# 14-DPLL_1.net
KiCad netlist of a schematic drawn in Altium Designer
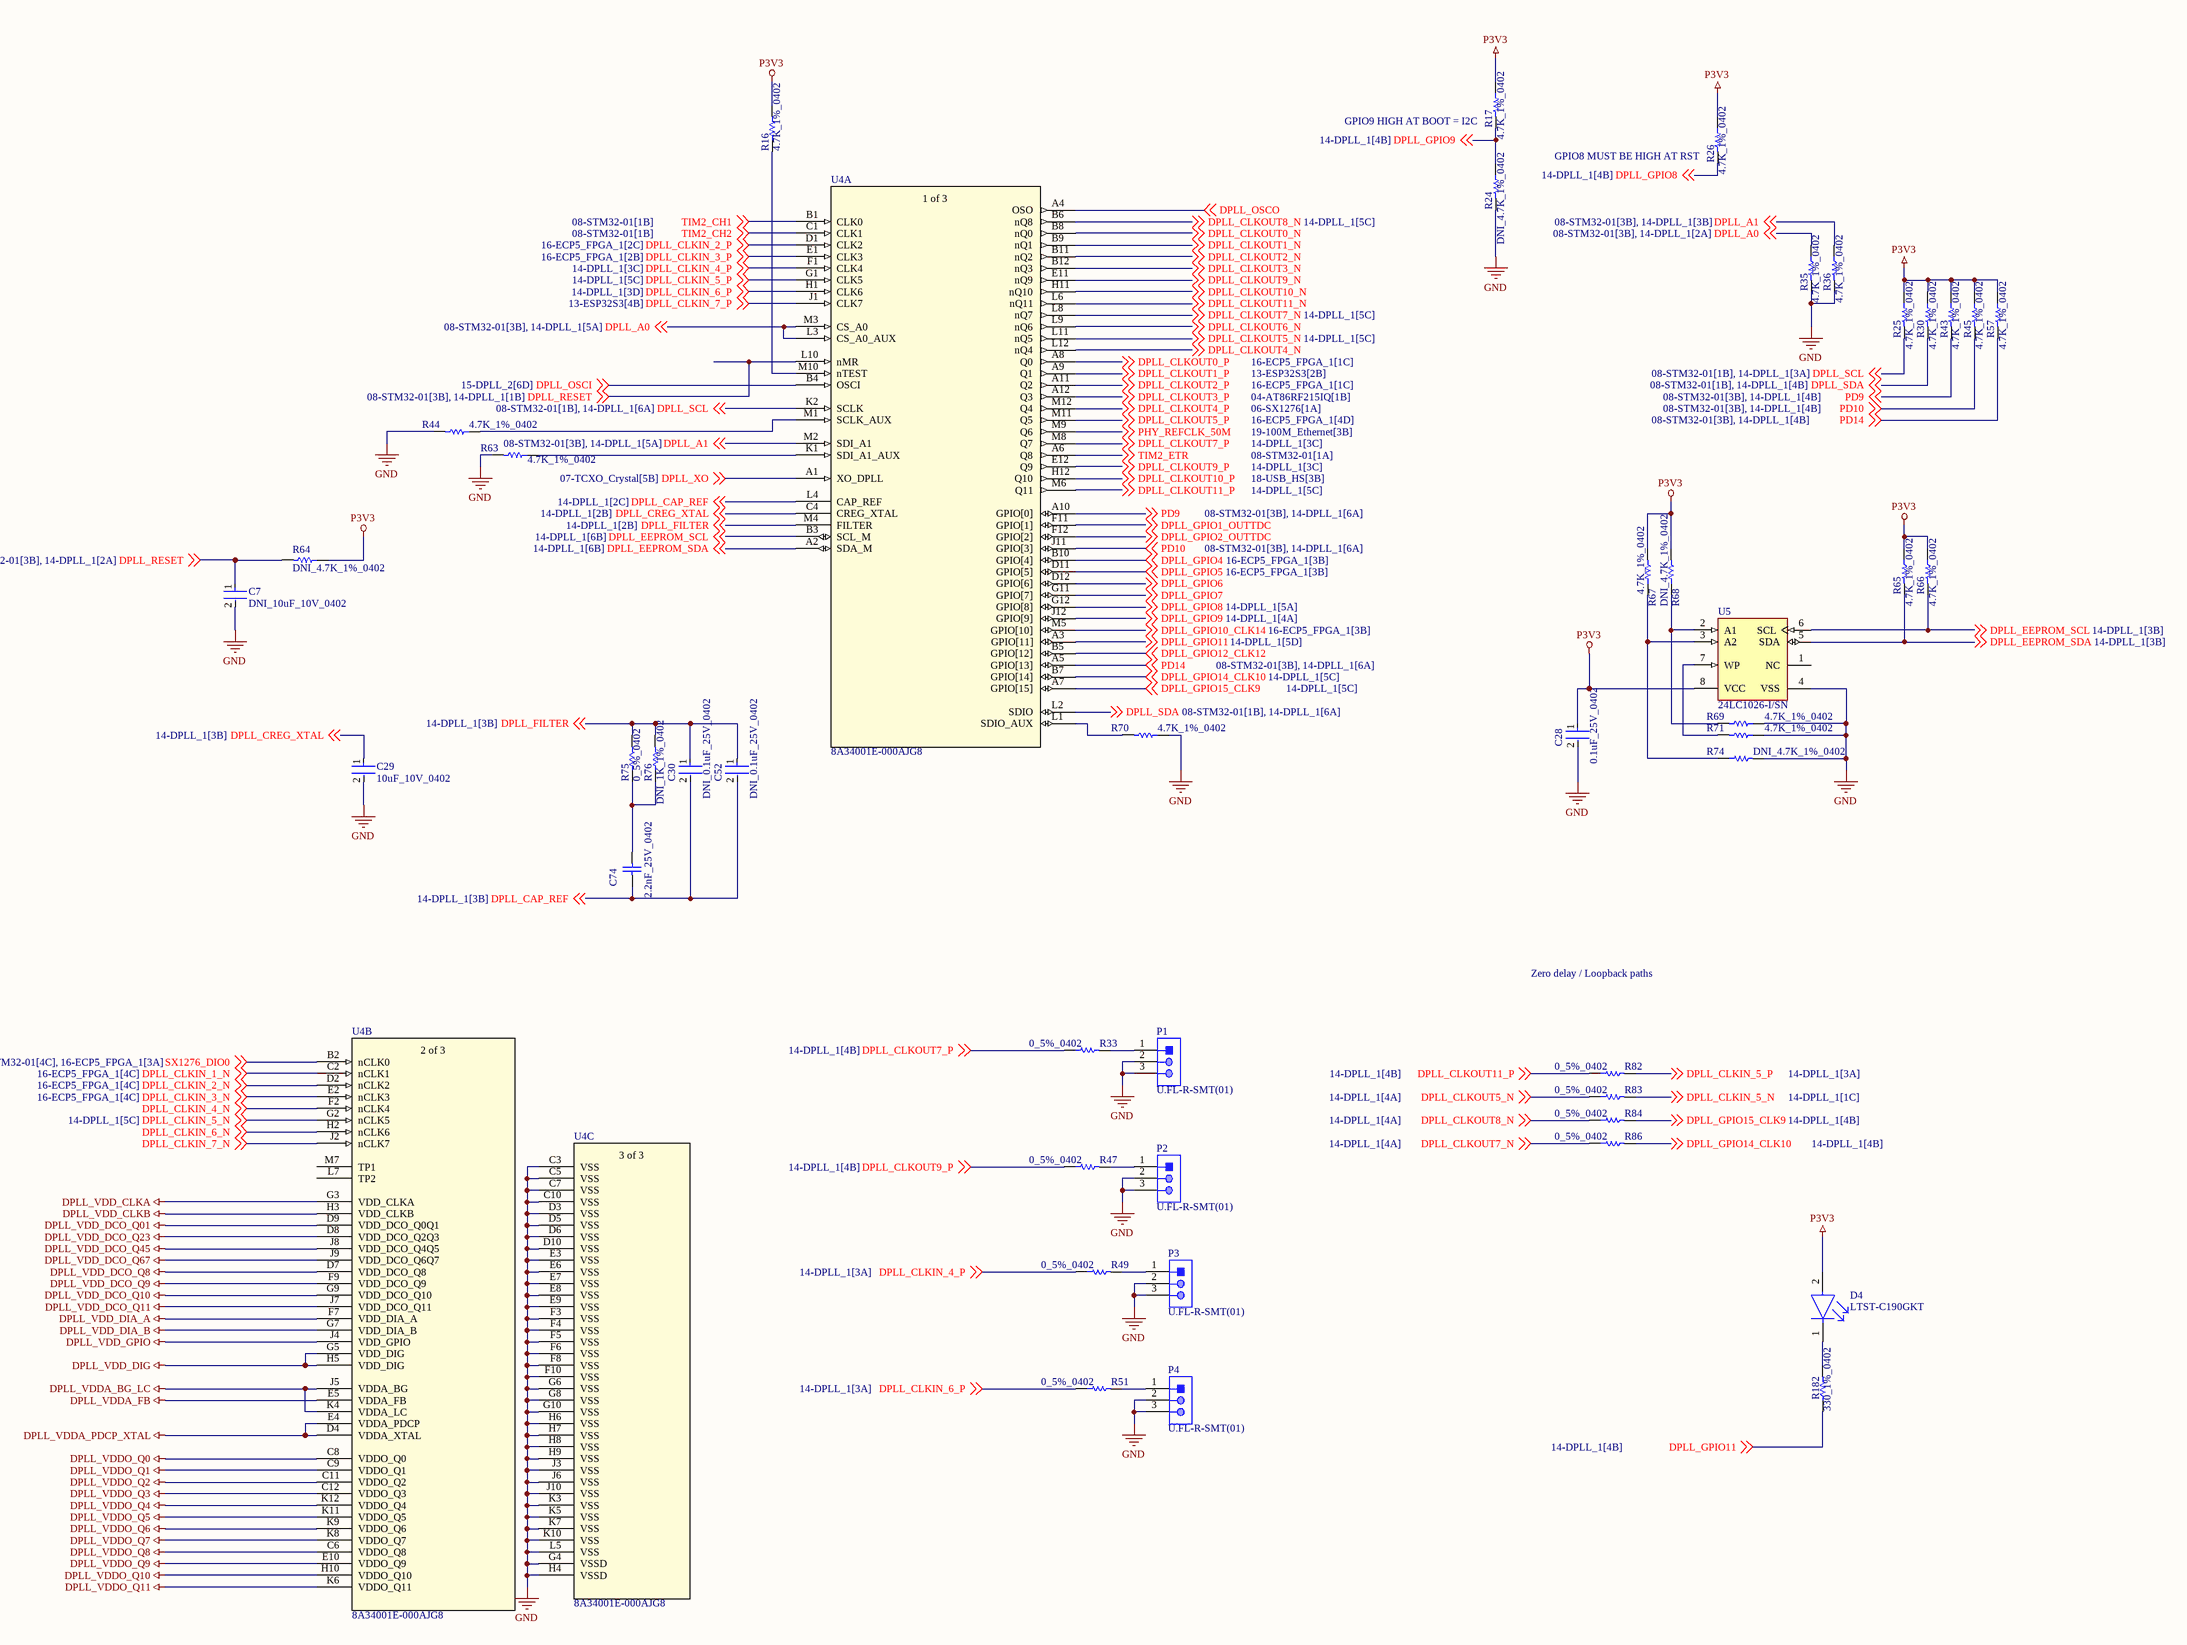
[diagram p0: 14-DPLL_1.SchDoc]

(export (version "E")
  (design (tool "Eeschema 10.0.6"))
  (components
    (comp (ref "C7")
      (value "DNI_10uF_10V_0402")
      (footprint "FP-CL05A106MP5NUNC-MFG")
      (description "CAP CER 10UF 10V X5R 0402")
      (fields
        (field (name "OCTOPART") "https://octopart.com/cl05a106mp5nunc-samsung-22457395")
        (field (name "TOLERANCE") "20%")
      )
      (libsource (lib "Altium Content Vault") (part "b4654b650e69147ec39a6b967a45e02"))
    )
    (comp (ref "C28")
      (value "0.1uF_25V_0402")
      (footprint "FP-0402-L_1_0_1-W_0_5_0_1-IPC_C")
      (description "General Purpose Ceramic Capacitor, 0402, 100nF, 10%, X7R, 15%, 25V")
      (fields (field (name "VOLTAGE") "25V") (field (name "TOLERANCE") "10%"))
      (libsource (lib "Altium Content Vault") (part "b4654b650e69147ec39a6b967a45e02"))
    )
    (comp (ref "C29")
      (value "10uF_10V_0402")
      (footprint "FP-CL05A106MP5NUNC-MFG")
      (description "CAP CER 10UF 10V X5R 0402")
      (fields
        (field (name "OCTOPART") "https://octopart.com/cl05a106mp5nunc-samsung-22457395")
        (field (name "TOLERANCE") "20%")
      )
      (libsource (lib "Altium Content Vault") (part "b4654b650e69147ec39a6b967a45e02"))
    )
    (comp (ref "C30")
      (value "DNI_0.1uF_25V_0402")
      (footprint "FP-0402-L_1_0_1-W_0_5_0_1-IPC_C")
      (description "General Purpose Ceramic Capacitor, 0402, 100nF, 10%, X7R, 15%, 25V")
      (fields (field (name "VOLTAGE") "25V") (field (name "TOLERANCE") "10%"))
      (libsource (lib "Altium Content Vault") (part "b4654b650e69147ec39a6b967a45e02"))
    )
    (comp (ref "C52")
      (value "DNI_0.1uF_25V_0402")
      (footprint "FP-0402-L_1_0_1-W_0_5_0_1-IPC_C")
      (description "General Purpose Ceramic Capacitor, 0402, 100nF, 10%, X7R, 15%, 25V")
      (fields (field (name "VOLTAGE") "25V") (field (name "TOLERANCE") "10%"))
      (libsource (lib "Altium Content Vault") (part "b4654b650e69147ec39a6b967a45e02"))
    )
    (comp (ref "C74")
      (value "2.2nF_25V_0402")
      (footprint "CAPC1005X56X25LL10T15")
      (fields
        (field (name "MANUFACTURER") "AVX Interconnect / Elco")
        (field (name "PART NUMBER") "04025C222JAT2A")
      )
      (libsource (lib "Altium Content Vault") (part "CAP"))
    )
    (comp (ref "D4")
      (value "LTST-C190GKT")
      (footprint "FP-LTST-C190GKT-MFG")
      (description "LED GREEN CLEAR CHIP SMD")
      (fields (field (name "VOLTAGE") "2V"))
      (libsource (lib "Altium Content Vault") (part "8706943c75ba83719d021d2fdc84c58"))
    )
    (comp (ref "P1")
      (value "U.FL-R-SMT(01)")
      (footprint "HRS-U.FL-R-SMT(10)_V")
      (description "CONN RECPT ULTRA-MINI COAX SMD")
      (fields (field (name "MANUFACTURER") "Hirose Electric") (field (name "APPROVAL CATEGORY") "UL94V-0"))
      (libsource (lib "Altium Content Vault") (part "CN-1P-M-R3"))
    )
    (comp (ref "P2")
      (value "U.FL-R-SMT(01)")
      (footprint "HRS-U.FL-R-SMT(10)_V")
      (description "CONN RECPT ULTRA-MINI COAX SMD")
      (fields (field (name "MANUFACTURER") "Hirose Electric") (field (name "APPROVAL CATEGORY") "UL94V-0"))
      (libsource (lib "Altium Content Vault") (part "CN-1P-M-R3"))
    )
    (comp (ref "P3")
      (value "U.FL-R-SMT(01)")
      (footprint "HRS-U.FL-R-SMT(10)_V")
      (description "CONN RECPT ULTRA-MINI COAX SMD")
      (fields (field (name "MANUFACTURER") "Hirose Electric") (field (name "APPROVAL CATEGORY") "UL94V-0"))
      (libsource (lib "Altium Content Vault") (part "CN-1P-M-R3"))
    )
    (comp (ref "P4")
      (value "U.FL-R-SMT(01)")
      (footprint "HRS-U.FL-R-SMT(10)_V")
      (description "CONN RECPT ULTRA-MINI COAX SMD")
      (fields (field (name "MANUFACTURER") "Hirose Electric") (field (name "APPROVAL CATEGORY") "UL94V-0"))
      (libsource (lib "Altium Content Vault") (part "CN-1P-M-R3"))
    )
    (comp (ref "R16")
      (value "4.7K_1%_0402")
      (footprint "RESC1005X40X25NL10T10")
      (fields (field (name "MANUFACTURER") "Bourns") (field (name "PART NUMBER") "CR0402-FX-4701GLF"))
      (libsource (lib "Altium Content Vault") (part "RES"))
    )
    (comp (ref "R17")
      (value "4.7K_1%_0402")
      (footprint "RESC1005X40X25NL10T10")
      (fields (field (name "MANUFACTURER") "Bourns") (field (name "PART NUMBER") "CR0402-FX-4701GLF"))
      (libsource (lib "Altium Content Vault") (part "RES"))
    )
    (comp (ref "R24")
      (value "DNI_4.7K_1%_0402")
      (footprint "RESC1005X40X25NL10T10")
      (fields (field (name "MANUFACTURER") "Bourns") (field (name "PART NUMBER") "CR0402-FX-4701GLF"))
      (libsource (lib "Altium Content Vault") (part "RES"))
    )
    (comp (ref "R25")
      (value "4.7K_1%_0402")
      (footprint "RESC1005X40X25NL10T10")
      (fields (field (name "MANUFACTURER") "Bourns") (field (name "PART NUMBER") "CR0402-FX-4701GLF"))
      (libsource (lib "Altium Content Vault") (part "RES"))
    )
    (comp (ref "R26")
      (value "4.7K_1%_0402")
      (footprint "RESC1005X40X25NL10T10")
      (fields (field (name "MANUFACTURER") "Bourns") (field (name "PART NUMBER") "CR0402-FX-4701GLF"))
      (libsource (lib "Altium Content Vault") (part "RES"))
    )
    (comp (ref "R30")
      (value "4.7K_1%_0402")
      (footprint "RESC1005X40X25NL10T10")
      (fields (field (name "MANUFACTURER") "Bourns") (field (name "PART NUMBER") "CR0402-FX-4701GLF"))
      (libsource (lib "Altium Content Vault") (part "RES"))
    )
    (comp (ref "R33")
      (value "0_5%_0402")
      (footprint "RESC1005X40X25LL10T10")
      (fields (field (name "MANUFACTURER") "KOA Speer") (field (name "PART NUMBER") "RK73Z1ETTP"))
      (libsource (lib "Altium Content Vault") (part "RES"))
    )
    (comp (ref "R35")
      (value "4.7K_1%_0402")
      (footprint "RESC1005X40X25NL10T10")
      (fields (field (name "MANUFACTURER") "Bourns") (field (name "PART NUMBER") "CR0402-FX-4701GLF"))
      (libsource (lib "Altium Content Vault") (part "RES"))
    )
    (comp (ref "R36")
      (value "4.7K_1%_0402")
      (footprint "RESC1005X40X25NL10T10")
      (fields (field (name "MANUFACTURER") "Bourns") (field (name "PART NUMBER") "CR0402-FX-4701GLF"))
      (libsource (lib "Altium Content Vault") (part "RES"))
    )
    (comp (ref "R43")
      (value "4.7K_1%_0402")
      (footprint "RESC1005X40X25NL10T10")
      (fields (field (name "MANUFACTURER") "Bourns") (field (name "PART NUMBER") "CR0402-FX-4701GLF"))
      (libsource (lib "Altium Content Vault") (part "RES"))
    )
    (comp (ref "R44")
      (value "4.7K_1%_0402")
      (footprint "RESC1005X40X25NL10T10")
      (fields (field (name "MANUFACTURER") "Bourns") (field (name "PART NUMBER") "CR0402-FX-4701GLF"))
      (libsource (lib "Altium Content Vault") (part "RES"))
    )
    (comp (ref "R45")
      (value "4.7K_1%_0402")
      (footprint "RESC1005X40X25NL10T10")
      (fields (field (name "MANUFACTURER") "Bourns") (field (name "PART NUMBER") "CR0402-FX-4701GLF"))
      (libsource (lib "Altium Content Vault") (part "RES"))
    )
    (comp (ref "R47")
      (value "0_5%_0402")
      (footprint "RESC1005X40X25LL10T10")
      (fields (field (name "MANUFACTURER") "KOA Speer") (field (name "PART NUMBER") "RK73Z1ETTP"))
      (libsource (lib "Altium Content Vault") (part "RES"))
    )
    (comp (ref "R49")
      (value "0_5%_0402")
      (footprint "RESC1005X40X25LL10T10")
      (fields (field (name "MANUFACTURER") "KOA Speer") (field (name "PART NUMBER") "RK73Z1ETTP"))
      (libsource (lib "Altium Content Vault") (part "RES"))
    )
    (comp (ref "R51")
      (value "0_5%_0402")
      (footprint "RESC1005X40X25LL10T10")
      (fields (field (name "MANUFACTURER") "KOA Speer") (field (name "PART NUMBER") "RK73Z1ETTP"))
      (libsource (lib "Altium Content Vault") (part "RES"))
    )
    (comp (ref "R57")
      (value "4.7K_1%_0402")
      (footprint "RESC1005X40X25NL10T10")
      (fields (field (name "MANUFACTURER") "Bourns") (field (name "PART NUMBER") "CR0402-FX-4701GLF"))
      (libsource (lib "Altium Content Vault") (part "RES"))
    )
    (comp (ref "R63")
      (value "4.7K_1%_0402")
      (footprint "RESC1005X40X25NL10T10")
      (fields (field (name "MANUFACTURER") "Bourns") (field (name "PART NUMBER") "CR0402-FX-4701GLF"))
      (libsource (lib "Altium Content Vault") (part "RES"))
    )
    (comp (ref "R64")
      (value "DNI_4.7K_1%_0402")
      (footprint "RESC1005X40X25NL10T10")
      (fields (field (name "MANUFACTURER") "Bourns") (field (name "PART NUMBER") "CR0402-FX-4701GLF"))
      (libsource (lib "Altium Content Vault") (part "RES"))
    )
    (comp (ref "R65")
      (value "4.7K_1%_0402")
      (footprint "RESC1005X40X25NL10T10")
      (fields (field (name "MANUFACTURER") "Bourns") (field (name "PART NUMBER") "CR0402-FX-4701GLF"))
      (libsource (lib "Altium Content Vault") (part "RES"))
    )
    (comp (ref "R66")
      (value "4.7K_1%_0402")
      (footprint "RESC1005X40X25NL10T10")
      (fields (field (name "MANUFACTURER") "Bourns") (field (name "PART NUMBER") "CR0402-FX-4701GLF"))
      (libsource (lib "Altium Content Vault") (part "RES"))
    )
    (comp (ref "R67")
      (value "4.7K_1%_0402")
      (footprint "RESC1005X40X25NL10T10")
      (fields (field (name "MANUFACTURER") "Bourns") (field (name "PART NUMBER") "CR0402-FX-4701GLF"))
      (libsource (lib "Altium Content Vault") (part "RES"))
    )
    (comp (ref "R68")
      (value "DNI_4.7K_1%_0402")
      (footprint "RESC1005X40X25NL10T10")
      (fields (field (name "MANUFACTURER") "Bourns") (field (name "PART NUMBER") "CR0402-FX-4701GLF"))
      (libsource (lib "Altium Content Vault") (part "RES"))
    )
    (comp (ref "R69")
      (value "4.7K_1%_0402")
      (footprint "RESC1005X40X25NL10T10")
      (fields (field (name "MANUFACTURER") "Bourns") (field (name "PART NUMBER") "CR0402-FX-4701GLF"))
      (libsource (lib "Altium Content Vault") (part "RES"))
    )
    (comp (ref "R70")
      (value "4.7K_1%_0402")
      (footprint "RESC1005X40X25NL10T10")
      (fields (field (name "MANUFACTURER") "Bourns") (field (name "PART NUMBER") "CR0402-FX-4701GLF"))
      (libsource (lib "Altium Content Vault") (part "RES"))
    )
    (comp (ref "R71")
      (value "4.7K_1%_0402")
      (footprint "RESC1005X40X25NL10T10")
      (fields (field (name "MANUFACTURER") "Bourns") (field (name "PART NUMBER") "CR0402-FX-4701GLF"))
      (libsource (lib "Altium Content Vault") (part "RES"))
    )
    (comp (ref "R74")
      (value "DNI_4.7K_1%_0402")
      (footprint "RESC1005X40X25NL10T10")
      (fields (field (name "MANUFACTURER") "Bourns") (field (name "PART NUMBER") "CR0402-FX-4701GLF"))
      (libsource (lib "Altium Content Vault") (part "RES"))
    )
    (comp (ref "R75")
      (value "0_5%_0402")
      (footprint "RESC1005X40X25LL10T10")
      (fields (field (name "MANUFACTURER") "KOA Speer") (field (name "PART NUMBER") "RK73Z1ETTP"))
      (libsource (lib "Altium Content Vault") (part "RES"))
    )
    (comp (ref "R76")
      (value "DNI_1K_1%_0402")
      (footprint "RESC1005X40X25NL05T05")
      (fields (field (name "MANUFACTURER") "Vishay Dale") (field (name "PART NUMBER") "CRCW04021K00FKTD"))
      (libsource (lib "Altium Content Vault") (part "RES"))
    )
    (comp (ref "R82")
      (value "0_5%_0402")
      (footprint "RESC1005X40X25LL10T10")
      (fields (field (name "MANUFACTURER") "KOA Speer") (field (name "PART NUMBER") "RK73Z1ETTP"))
      (libsource (lib "Altium Content Vault") (part "RES"))
    )
    (comp (ref "R83")
      (value "0_5%_0402")
      (footprint "RESC1005X40X25LL10T10")
      (fields (field (name "MANUFACTURER") "KOA Speer") (field (name "PART NUMBER") "RK73Z1ETTP"))
      (libsource (lib "Altium Content Vault") (part "RES"))
    )
    (comp (ref "R84")
      (value "0_5%_0402")
      (footprint "RESC1005X40X25LL10T10")
      (fields (field (name "MANUFACTURER") "KOA Speer") (field (name "PART NUMBER") "RK73Z1ETTP"))
      (libsource (lib "Altium Content Vault") (part "RES"))
    )
    (comp (ref "R86")
      (value "0_5%_0402")
      (footprint "RESC1005X40X25LL10T10")
      (fields (field (name "MANUFACTURER") "KOA Speer") (field (name "PART NUMBER") "RK73Z1ETTP"))
      (libsource (lib "Altium Content Vault") (part "RES"))
    )
    (comp (ref "R182")
      (value "330_1%_0402")
      (footprint "RESC1005X40X25NL10T10")
      (fields (field (name "MANUFACTURER") "Panasonic") (field (name "PART NUMBER") "ERA-2AED331X"))
      (libsource (lib "Altium Content Vault") (part "RES"))
    )
    (comp (ref "U4")
      (value "8A34001E-000AJG8")
      (footprint "144-CABGA_REN")
      (description "No Description Available")
      (fields (field (name "COPYRIGHT") "Copyright (C) 2024 Ultra Librarian. All rights reserved."))
      (libsource (lib "8A34001E-000AJG8") (part "8A34001E-000AJG8"))
    )
    (comp (ref "U5")
      (value "24LC1026-I/SN")
      (footprint "MCHP-SOIC-SN8_N")
      (description "1024K bits I2C™ Serial EEPROM, 2.5 to 5.5 V, 400 kHz, -40 to 85 degC, 8-pin SOIC (SN8), Tube")
      (fields (field (name "MANUFACTURER") "Microchip"))
      (libsource (lib "Altium Content Vault") (part "MCHP-24LC1026-SOIC-8"))
    )
  )
  (nets
    (net (code "1") (name "DPLL_A0") (class "Default")
      (node (ref "R35") (pin "1") (pinfunction "1_1") (pintype "passive"))
      (node (ref "U4") (pin "L3") (pinfunction "CS_A0_AUX_L3") (pintype "input"))
      (node (ref "U4") (pin "M3") (pinfunction "CS_A0_M3") (pintype "input"))
    )
    (net (code "2") (name "DPLL_A1") (class "Default")
      (node (ref "R36") (pin "1") (pinfunction "1_1") (pintype "passive"))
      (node (ref "U4") (pin "M2") (pinfunction "SDI_A1_M2") (pintype "input"))
    )
    (net (code "3") (name "DPLL_CAP_REF") (class "Default")
      (node (ref "C30") (pin "2") (pinfunction "2_2") (pintype "passive"))
      (node (ref "C52") (pin "2") (pinfunction "2_2") (pintype "passive"))
      (node (ref "C74") (pin "1") (pinfunction "1_1") (pintype "passive"))
      (node (ref "U4") (pin "L4") (pinfunction "CAP_REF_L4") (pintype "passive"))
    )
    (net (code "4") (name "DPLL_CLKIN_1_N") (class "Default")
      (node (ref "U4") (pin "C2") (pinfunction "nCLK1_C2") (pintype "input"))
    )
    (net (code "5") (name "DPLL_CLKIN_2_N") (class "Default")
      (node (ref "U4") (pin "D2") (pinfunction "nCLK2_D2") (pintype "input"))
    )
    (net (code "6") (name "DPLL_CLKIN_2_P") (class "Default")
      (node (ref "U4") (pin "D1") (pinfunction "CLK2_D1") (pintype "input"))
    )
    (net (code "7") (name "DPLL_CLKIN_3_N") (class "Default")
      (node (ref "U4") (pin "E2") (pinfunction "nCLK3_E2") (pintype "input"))
    )
    (net (code "8") (name "DPLL_CLKIN_3_P") (class "Default")
      (node (ref "U4") (pin "E1") (pinfunction "CLK3_E1") (pintype "input"))
    )
    (net (code "9") (name "DPLL_CLKIN_4_N") (class "Default")
      (node (ref "U4") (pin "F2") (pinfunction "nCLK4_F2") (pintype "input"))
    )
    (net (code "10") (name "DPLL_CLKIN_4_P") (class "Default")
      (node (ref "R49") (pin "1") (pinfunction "1_1") (pintype "passive"))
      (node (ref "U4") (pin "F1") (pinfunction "CLK4_F1") (pintype "input"))
    )
    (net (code "11") (name "DPLL_CLKIN_5_N") (class "Default")
      (node (ref "R83") (pin "2") (pinfunction "2_2") (pintype "passive"))
      (node (ref "U4") (pin "G2") (pinfunction "nCLK5_G2") (pintype "input"))
    )
    (net (code "12") (name "DPLL_CLKIN_5_P") (class "Default")
      (node (ref "R82") (pin "2") (pinfunction "2_2") (pintype "passive"))
      (node (ref "U4") (pin "G1") (pinfunction "CLK5_G1") (pintype "input"))
    )
    (net (code "13") (name "DPLL_CLKIN_6_N") (class "Default")
      (node (ref "U4") (pin "H2") (pinfunction "nCLK6_H2") (pintype "input"))
    )
    (net (code "14") (name "DPLL_CLKIN_6_P") (class "Default")
      (node (ref "R51") (pin "1") (pinfunction "1_1") (pintype "passive"))
      (node (ref "U4") (pin "H1") (pinfunction "CLK6_H1") (pintype "input"))
    )
    (net (code "15") (name "DPLL_CLKIN_7_N") (class "Default")
      (node (ref "U4") (pin "J2") (pinfunction "nCLK7_J2") (pintype "input"))
    )
    (net (code "16") (name "DPLL_CLKIN_7_P") (class "Default")
      (node (ref "U4") (pin "J1") (pinfunction "CLK7_J1") (pintype "input"))
    )
    (net (code "17") (name "DPLL_CLKOUT0_N") (class "Default")
      (node (ref "U4") (pin "B8") (pinfunction "nQ0_B8") (pintype "output"))
    )
    (net (code "18") (name "DPLL_CLKOUT0_P") (class "Default")
      (node (ref "U4") (pin "A8") (pinfunction "Q0_A8") (pintype "output"))
    )
    (net (code "19") (name "DPLL_CLKOUT1_N") (class "Default")
      (node (ref "U4") (pin "B9") (pinfunction "nQ1_B9") (pintype "output"))
    )
    (net (code "20") (name "DPLL_CLKOUT1_P") (class "Default")
      (node (ref "U4") (pin "A9") (pinfunction "Q1_A9") (pintype "output"))
    )
    (net (code "21") (name "DPLL_CLKOUT2_N") (class "Default")
      (node (ref "U4") (pin "B11") (pinfunction "nQ2_B11") (pintype "output"))
    )
    (net (code "22") (name "DPLL_CLKOUT2_P") (class "Default")
      (node (ref "U4") (pin "A11") (pinfunction "Q2_A11") (pintype "output"))
    )
    (net (code "23") (name "DPLL_CLKOUT3_N") (class "Default")
      (node (ref "U4") (pin "B12") (pinfunction "nQ3_B12") (pintype "output"))
    )
    (net (code "24") (name "DPLL_CLKOUT3_P") (class "Default")
      (node (ref "U4") (pin "A12") (pinfunction "Q3_A12") (pintype "output"))
    )
    (net (code "25") (name "DPLL_CLKOUT4_N") (class "Default")
      (node (ref "U4") (pin "L12") (pinfunction "nQ4_L12") (pintype "output"))
    )
    (net (code "26") (name "DPLL_CLKOUT4_P") (class "Default")
      (node (ref "U4") (pin "M12") (pinfunction "Q4_M12") (pintype "output"))
    )
    (net (code "27") (name "DPLL_CLKOUT5_N") (class "Default")
      (node (ref "R83") (pin "1") (pinfunction "1_1") (pintype "passive"))
      (node (ref "U4") (pin "L11") (pinfunction "nQ5_L11") (pintype "output"))
    )
    (net (code "28") (name "DPLL_CLKOUT5_P") (class "Default")
      (node (ref "U4") (pin "M11") (pinfunction "Q5_M11") (pintype "output"))
    )
    (net (code "29") (name "DPLL_CLKOUT6_N") (class "Default")
      (node (ref "U4") (pin "L9") (pinfunction "nQ6_L9") (pintype "output"))
    )
    (net (code "30") (name "DPLL_CLKOUT7_N") (class "Default")
      (node (ref "R86") (pin "1") (pinfunction "1_1") (pintype "passive"))
      (node (ref "U4") (pin "L8") (pinfunction "nQ7_L8") (pintype "output"))
    )
    (net (code "31") (name "DPLL_CLKOUT7_P") (class "Default")
      (node (ref "R33") (pin "1") (pinfunction "1_1") (pintype "passive"))
      (node (ref "U4") (pin "M8") (pinfunction "Q7_M8") (pintype "output"))
    )
    (net (code "32") (name "DPLL_CLKOUT8_N") (class "Default")
      (node (ref "R84") (pin "1") (pinfunction "1_1") (pintype "passive"))
      (node (ref "U4") (pin "B6") (pinfunction "nQ8_B6") (pintype "output"))
    )
    (net (code "33") (name "DPLL_CLKOUT9_N") (class "Default")
      (node (ref "U4") (pin "E11") (pinfunction "nQ9_E11") (pintype "output"))
    )
    (net (code "34") (name "DPLL_CLKOUT9_P") (class "Default")
      (node (ref "R47") (pin "1") (pinfunction "1_1") (pintype "passive"))
      (node (ref "U4") (pin "E12") (pinfunction "Q9_E12") (pintype "output"))
    )
    (net (code "35") (name "DPLL_CLKOUT10_N") (class "Default")
      (node (ref "U4") (pin "H11") (pinfunction "nQ10_H11") (pintype "output"))
    )
    (net (code "36") (name "DPLL_CLKOUT10_P") (class "Default")
      (node (ref "U4") (pin "H12") (pinfunction "Q10_H12") (pintype "output"))
    )
    (net (code "37") (name "DPLL_CLKOUT11_N") (class "Default")
      (node (ref "U4") (pin "L6") (pinfunction "nQ11_L6") (pintype "output"))
    )
    (net (code "38") (name "DPLL_CLKOUT11_P") (class "Default")
      (node (ref "R82") (pin "1") (pinfunction "1_1") (pintype "passive"))
      (node (ref "U4") (pin "M6") (pinfunction "Q11_M6") (pintype "output"))
    )
    (net (code "39") (name "DPLL_CREG_XTAL") (class "Default")
      (node (ref "C29") (pin "1") (pinfunction "1_1") (pintype "passive"))
      (node (ref "U4") (pin "C4") (pinfunction "CREG_XTAL_C4") (pintype "passive"))
    )
    (net (code "40") (name "DPLL_EEPROM_SCL") (class "Default")
      (node (ref "R66") (pin "2") (pinfunction "2_2") (pintype "passive"))
      (node (ref "U4") (pin "B3") (pinfunction "SCL_M_B3") (pintype "bidirectional"))
      (node (ref "U5") (pin "6") (pinfunction "SCL_6") (pintype "input"))
    )
    (net (code "41") (name "DPLL_EEPROM_SDA") (class "Default")
      (node (ref "R65") (pin "2") (pinfunction "2_2") (pintype "passive"))
      (node (ref "U4") (pin "A2") (pinfunction "SDA_M_A2") (pintype "bidirectional"))
      (node (ref "U5") (pin "5") (pinfunction "SDA_5") (pintype "bidirectional"))
    )
    (net (code "42") (name "DPLL_FILTER") (class "Default")
      (node (ref "C30") (pin "1") (pinfunction "1_1") (pintype "passive"))
      (node (ref "C52") (pin "1") (pinfunction "1_1") (pintype "passive"))
      (node (ref "R75") (pin "2") (pinfunction "2_2") (pintype "passive"))
      (node (ref "R76") (pin "2") (pinfunction "2_2") (pintype "passive"))
      (node (ref "U4") (pin "M4") (pinfunction "FILTER_M4") (pintype "passive"))
    )
    (net (code "43") (name "DPLL_GPIO1_OUTTDC") (class "Default")
      (node (ref "U4") (pin "F11") (pinfunction "GPIO[1]_F11") (pintype "bidirectional"))
    )
    (net (code "44") (name "DPLL_GPIO2_OUTTDC") (class "Default")
      (node (ref "U4") (pin "F12") (pinfunction "GPIO[2]_F12") (pintype "bidirectional"))
    )
    (net (code "45") (name "DPLL_GPIO4") (class "Default")
      (node (ref "U4") (pin "B10") (pinfunction "GPIO[4]_B10") (pintype "bidirectional"))
    )
    (net (code "46") (name "DPLL_GPIO5") (class "Default")
      (node (ref "U4") (pin "D11") (pinfunction "GPIO[5]_D11") (pintype "bidirectional"))
    )
    (net (code "47") (name "DPLL_GPIO6") (class "Default")
      (node (ref "U4") (pin "D12") (pinfunction "GPIO[6]_D12") (pintype "bidirectional"))
    )
    (net (code "48") (name "DPLL_GPIO7") (class "Default")
      (node (ref "U4") (pin "G11") (pinfunction "GPIO[7]_G11") (pintype "bidirectional"))
    )
    (net (code "49") (name "DPLL_GPIO8") (class "Default")
      (node (ref "R26") (pin "2") (pinfunction "2_2") (pintype "passive"))
      (node (ref "U4") (pin "G12") (pinfunction "GPIO[8]_G12") (pintype "bidirectional"))
    )
    (net (code "50") (name "DPLL_GPIO9") (class "Default")
      (node (ref "R17") (pin "2") (pinfunction "2_2") (pintype "passive"))
      (node (ref "R24") (pin "1") (pinfunction "1_1") (pintype "passive"))
      (node (ref "U4") (pin "J12") (pinfunction "GPIO[9]_J12") (pintype "bidirectional"))
    )
    (net (code "51") (name "DPLL_GPIO10_CLK14") (class "Default")
      (node (ref "U4") (pin "M5") (pinfunction "GPIO[10]_M5") (pintype "bidirectional"))
    )
    (net (code "52") (name "DPLL_GPIO11") (class "Default")
      (node (ref "R182") (pin "1") (pinfunction "1_1") (pintype "passive"))
      (node (ref "U4") (pin "A3") (pinfunction "GPIO[11]_A3") (pintype "bidirectional"))
    )
    (net (code "53") (name "DPLL_GPIO12_CLK12") (class "Default")
      (node (ref "U4") (pin "B5") (pinfunction "GPIO[12]_B5") (pintype "bidirectional"))
    )
    (net (code "54") (name "DPLL_GPIO14_CLK10") (class "Default")
      (node (ref "R86") (pin "2") (pinfunction "2_2") (pintype "passive"))
      (node (ref "U4") (pin "B7") (pinfunction "GPIO[14]_B7") (pintype "bidirectional"))
    )
    (net (code "55") (name "DPLL_GPIO15_CLK9") (class "Default")
      (node (ref "R84") (pin "2") (pinfunction "2_2") (pintype "passive"))
      (node (ref "U4") (pin "A7") (pinfunction "GPIO[15]_A7") (pintype "bidirectional"))
    )
    (net (code "56") (name "DPLL_OSCI") (class "Default")
      (node (ref "U4") (pin "B4") (pinfunction "OSCI_B4") (pintype "input"))
    )
    (net (code "57") (name "DPLL_OSCO") (class "Default")
      (node (ref "U4") (pin "A4") (pinfunction "OSO_A4") (pintype "output"))
    )
    (net (code "58") (name "DPLL_RESET") (class "Default")
      (node (ref "C7") (pin "1") (pinfunction "1_1") (pintype "passive"))
      (node (ref "R64") (pin "2") (pinfunction "2_2") (pintype "passive"))
      (node (ref "U4") (pin "L10") (pinfunction "nMR_L10") (pintype "input"))
    )
    (net (code "59") (name "DPLL_SCL") (class "Default")
      (node (ref "R25") (pin "2") (pinfunction "2_2") (pintype "passive"))
      (node (ref "U4") (pin "K2") (pinfunction "SCLK_K2") (pintype "input"))
    )
    (net (code "60") (name "DPLL_SDA") (class "Default")
      (node (ref "R30") (pin "2") (pinfunction "2_2") (pintype "passive"))
      (node (ref "U4") (pin "L2") (pinfunction "SDIO_L2") (pintype "bidirectional"))
    )
    (net (code "61") (name "DPLL_VDDA_BG_LC") (class "Default")
      (node (ref "U4") (pin "J5") (pinfunction "VDDA_BG_J5") (pintype "power_in"))
      (node (ref "U4") (pin "K4") (pinfunction "VDDA_LC_K4") (pintype "power_in"))
    )
    (net (code "62") (name "DPLL_VDDA_FB") (class "Default")
      (node (ref "U4") (pin "E5") (pinfunction "VDDA_FB_E5") (pintype "power_in"))
    )
    (net (code "63") (name "DPLL_VDDA_PDCP_XTAL") (class "Default")
      (node (ref "U4") (pin "D4") (pinfunction "VDDA_XTAL_D4") (pintype "power_in"))
      (node (ref "U4") (pin "E4") (pinfunction "VDDA_PDCP_E4") (pintype "power_in"))
    )
    (net (code "64") (name "DPLL_VDDO_Q0") (class "Default")
      (node (ref "U4") (pin "C8") (pinfunction "VDDO_Q0_C8") (pintype "power_in"))
    )
    (net (code "65") (name "DPLL_VDDO_Q1") (class "Default")
      (node (ref "U4") (pin "C9") (pinfunction "VDDO_Q1_C9") (pintype "power_in"))
    )
    (net (code "66") (name "DPLL_VDDO_Q2") (class "Default")
      (node (ref "U4") (pin "C11") (pinfunction "VDDO_Q2_C11") (pintype "power_in"))
    )
    (net (code "67") (name "DPLL_VDDO_Q3") (class "Default")
      (node (ref "U4") (pin "C12") (pinfunction "VDDO_Q3_C12") (pintype "power_in"))
    )
    (net (code "68") (name "DPLL_VDDO_Q4") (class "Default")
      (node (ref "U4") (pin "K12") (pinfunction "VDDO_Q4_K12") (pintype "power_in"))
    )
    (net (code "69") (name "DPLL_VDDO_Q5") (class "Default")
      (node (ref "U4") (pin "K11") (pinfunction "VDDO_Q5_K11") (pintype "power_in"))
    )
    (net (code "70") (name "DPLL_VDDO_Q6") (class "Default")
      (node (ref "U4") (pin "K9") (pinfunction "VDDO_Q6_K9") (pintype "power_in"))
    )
    (net (code "71") (name "DPLL_VDDO_Q7") (class "Default")
      (node (ref "U4") (pin "K8") (pinfunction "VDDO_Q7_K8") (pintype "power_in"))
    )
    (net (code "72") (name "DPLL_VDDO_Q8") (class "Default")
      (node (ref "U4") (pin "C6") (pinfunction "VDDO_Q8_C6") (pintype "power_in"))
    )
    (net (code "73") (name "DPLL_VDDO_Q9") (class "Default")
      (node (ref "U4") (pin "E10") (pinfunction "VDDO_Q9_E10") (pintype "power_in"))
    )
    (net (code "74") (name "DPLL_VDDO_Q10") (class "Default")
      (node (ref "U4") (pin "H10") (pinfunction "VDDO_Q10_H10") (pintype "power_in"))
    )
    (net (code "75") (name "DPLL_VDDO_Q11") (class "Default")
      (node (ref "U4") (pin "K6") (pinfunction "VDDO_Q11_K6") (pintype "power_in"))
    )
    (net (code "76") (name "DPLL_VDD_CLKA") (class "Default")
      (node (ref "U4") (pin "G3") (pinfunction "VDD_CLKA_G3") (pintype "power_in"))
    )
    (net (code "77") (name "DPLL_VDD_CLKB") (class "Default")
      (node (ref "U4") (pin "H3") (pinfunction "VDD_CLKB_H3") (pintype "power_in"))
    )
    (net (code "78") (name "DPLL_VDD_DCO_Q01") (class "Default")
      (node (ref "U4") (pin "D9") (pinfunction "VDD_DCO_Q0Q1_D9") (pintype "power_in"))
    )
    (net (code "79") (name "DPLL_VDD_DCO_Q8") (class "Default")
      (node (ref "U4") (pin "D7") (pinfunction "VDD_DCO_Q8_D7") (pintype "power_in"))
    )
    (net (code "80") (name "DPLL_VDD_DCO_Q9") (class "Default")
      (node (ref "U4") (pin "F9") (pinfunction "VDD_DCO_Q9_F9") (pintype "power_in"))
    )
    (net (code "81") (name "DPLL_VDD_DCO_Q10") (class "Default")
      (node (ref "U4") (pin "G9") (pinfunction "VDD_DCO_Q10_G9") (pintype "power_in"))
    )
    (net (code "82") (name "DPLL_VDD_DCO_Q11") (class "Default")
      (node (ref "U4") (pin "J7") (pinfunction "VDD_DCO_Q11_J7") (pintype "power_in"))
    )
    (net (code "83") (name "DPLL_VDD_DCO_Q23") (class "Default")
      (node (ref "U4") (pin "D8") (pinfunction "VDD_DCO_Q2Q3_D8") (pintype "power_in"))
    )
    (net (code "84") (name "DPLL_VDD_DCO_Q45") (class "Default")
      (node (ref "U4") (pin "J8") (pinfunction "VDD_DCO_Q4Q5_J8") (pintype "power_in"))
    )
    (net (code "85") (name "DPLL_VDD_DCO_Q67") (class "Default")
      (node (ref "U4") (pin "J9") (pinfunction "VDD_DCO_Q6Q7_J9") (pintype "power_in"))
    )
    (net (code "86") (name "DPLL_VDD_DIA_A") (class "Default")
      (node (ref "U4") (pin "F7") (pinfunction "VDD_DIA_A_F7") (pintype "power_in"))
    )
    (net (code "87") (name "DPLL_VDD_DIA_B") (class "Default")
      (node (ref "U4") (pin "G7") (pinfunction "VDD_DIA_B_G7") (pintype "power_in"))
    )
    (net (code "88") (name "DPLL_VDD_DIG") (class "Default")
      (node (ref "U4") (pin "G5") (pinfunction "VDD_DIG_G5") (pintype "power_in"))
      (node (ref "U4") (pin "H5") (pinfunction "VDD_DIG_H5") (pintype "power_in"))
    )
    (net (code "89") (name "DPLL_VDD_GPIO") (class "Default")
      (node (ref "U4") (pin "J4") (pinfunction "VDD_GPIO_J4") (pintype "power_in"))
    )
    (net (code "90") (name "DPLL_XO") (class "Default")
      (node (ref "U4") (pin "A1") (pinfunction "XO_DPLL_A1") (pintype "input"))
    )
    (net (code "91") (name "GND") (class "Default")
      (node (ref "C28") (pin "2") (pinfunction "2_2") (pintype "passive"))
      (node (ref "C29") (pin "2") (pinfunction "2_2") (pintype "passive"))
      (node (ref "C7") (pin "2") (pinfunction "2_2") (pintype "passive"))
      (node (ref "P1") (pin "2") (pinfunction "2_2") (pintype "passive"))
      (node (ref "P1") (pin "3") (pinfunction "3_3") (pintype "passive"))
      (node (ref "P2") (pin "2") (pinfunction "2_2") (pintype "passive"))
      (node (ref "P2") (pin "3") (pinfunction "3_3") (pintype "passive"))
      (node (ref "P3") (pin "2") (pinfunction "2_2") (pintype "passive"))
      (node (ref "P3") (pin "3") (pinfunction "3_3") (pintype "passive"))
      (node (ref "P4") (pin "2") (pinfunction "2_2") (pintype "passive"))
      (node (ref "P4") (pin "3") (pinfunction "3_3") (pintype "passive"))
      (node (ref "R24") (pin "2") (pinfunction "2_2") (pintype "passive"))
      (node (ref "R35") (pin "2") (pinfunction "2_2") (pintype "passive"))
      (node (ref "R36") (pin "2") (pinfunction "2_2") (pintype "passive"))
      (node (ref "R44") (pin "2") (pinfunction "2_2") (pintype "passive"))
      (node (ref "R63") (pin "2") (pinfunction "2_2") (pintype "passive"))
      (node (ref "R69") (pin "1") (pinfunction "1_1") (pintype "passive"))
      (node (ref "R70") (pin "1") (pinfunction "1_1") (pintype "passive"))
      (node (ref "R71") (pin "1") (pinfunction "1_1") (pintype "passive"))
      (node (ref "R74") (pin "2") (pinfunction "2_2") (pintype "passive"))
      (node (ref "U4") (pin "C10") (pinfunction "VSS_C10") (pintype "power_in"))
      (node (ref "U4") (pin "C3") (pinfunction "VSS_C3") (pintype "power_in"))
      (node (ref "U4") (pin "C5") (pinfunction "VSS_C5") (pintype "power_in"))
      (node (ref "U4") (pin "C7") (pinfunction "VSS_C7") (pintype "power_in"))
      (node (ref "U4") (pin "D10") (pinfunction "VSS_D10") (pintype "power_in"))
      (node (ref "U4") (pin "D3") (pinfunction "VSS_D3") (pintype "power_in"))
      (node (ref "U4") (pin "D5") (pinfunction "VSS_D5") (pintype "power_in"))
      (node (ref "U4") (pin "D6") (pinfunction "VSS_D6") (pintype "power_in"))
      (node (ref "U4") (pin "E3") (pinfunction "VSS_E3") (pintype "power_in"))
      (node (ref "U4") (pin "E6") (pinfunction "VSS_E6") (pintype "power_in"))
      (node (ref "U4") (pin "E7") (pinfunction "VSS_E7") (pintype "power_in"))
      (node (ref "U4") (pin "E8") (pinfunction "VSS_E8") (pintype "power_in"))
      (node (ref "U4") (pin "E9") (pinfunction "VSS_E9") (pintype "power_in"))
      (node (ref "U4") (pin "F10") (pinfunction "VSS_F10") (pintype "power_in"))
      (node (ref "U4") (pin "F3") (pinfunction "VSS_F3") (pintype "power_in"))
      (node (ref "U4") (pin "F4") (pinfunction "VSS_F4") (pintype "power_in"))
      (node (ref "U4") (pin "F5") (pinfunction "VSS_F5") (pintype "power_in"))
      (node (ref "U4") (pin "F6") (pinfunction "VSS_F6") (pintype "power_in"))
      (node (ref "U4") (pin "F8") (pinfunction "VSS_F8") (pintype "power_in"))
      (node (ref "U4") (pin "G10") (pinfunction "VSS_G10") (pintype "power_in"))
      (node (ref "U4") (pin "G4") (pinfunction "VSSD_G4") (pintype "power_in"))
      (node (ref "U4") (pin "G6") (pinfunction "VSS_G6") (pintype "power_in"))
      (node (ref "U4") (pin "G8") (pinfunction "VSS_G8") (pintype "power_in"))
      (node (ref "U4") (pin "H4") (pinfunction "VSSD_H4") (pintype "power_in"))
      (node (ref "U4") (pin "H6") (pinfunction "VSS_H6") (pintype "power_in"))
      (node (ref "U4") (pin "H7") (pinfunction "VSS_H7") (pintype "power_in"))
      (node (ref "U4") (pin "H8") (pinfunction "VSS_H8") (pintype "power_in"))
      (node (ref "U4") (pin "H9") (pinfunction "VSS_H9") (pintype "power_in"))
      (node (ref "U4") (pin "J10") (pinfunction "VSS_J10") (pintype "power_in"))
      (node (ref "U4") (pin "J3") (pinfunction "VSS_J3") (pintype "power_in"))
      (node (ref "U4") (pin "J6") (pinfunction "VSS_J6") (pintype "power_in"))
      (node (ref "U4") (pin "K10") (pinfunction "VSS_K10") (pintype "power_in"))
      (node (ref "U4") (pin "K3") (pinfunction "VSS_K3") (pintype "power_in"))
      (node (ref "U4") (pin "K5") (pinfunction "VSS_K5") (pintype "power_in"))
      (node (ref "U4") (pin "K7") (pinfunction "VSS_K7") (pintype "power_in"))
      (node (ref "U4") (pin "L5") (pinfunction "VSS_L5") (pintype "power_in"))
      (node (ref "U5") (pin "4") (pinfunction "VSS_4") (pintype "power_in"))
    )
    (net (code "92") (name "Net-(C74-Pad2)") (class "Default")
      (node (ref "C74") (pin "2") (pinfunction "2_2") (pintype "passive"))
      (node (ref "R75") (pin "1") (pinfunction "1_1") (pintype "passive"))
      (node (ref "R76") (pin "1") (pinfunction "1_1") (pintype "passive"))
    )
    (net (code "93") (name "Net-(D4-C)") (class "Default")
      (node (ref "D4") (pin "1") (pinfunction "C_1") (pintype "passive"))
      (node (ref "R182") (pin "2") (pinfunction "2_2") (pintype "passive"))
    )
    (net (code "94") (name "Net-(P1-Pad1)") (class "Default")
      (node (ref "P1") (pin "1") (pinfunction "1_1") (pintype "passive"))
      (node (ref "R33") (pin "2") (pinfunction "2_2") (pintype "passive"))
    )
    (net (code "95") (name "Net-(P2-Pad1)") (class "Default")
      (node (ref "P2") (pin "1") (pinfunction "1_1") (pintype "passive"))
      (node (ref "R47") (pin "2") (pinfunction "2_2") (pintype "passive"))
    )
    (net (code "96") (name "Net-(P3-Pad1)") (class "Default")
      (node (ref "P3") (pin "1") (pinfunction "1_1") (pintype "passive"))
      (node (ref "R49") (pin "2") (pinfunction "2_2") (pintype "passive"))
    )
    (net (code "97") (name "Net-(P4-Pad1)") (class "Default")
      (node (ref "P4") (pin "1") (pinfunction "1_1") (pintype "passive"))
      (node (ref "R51") (pin "2") (pinfunction "2_2") (pintype "passive"))
    )
    (net (code "98") (name "Net-(U4A-SCLK_AUX)") (class "Default")
      (node (ref "R44") (pin "1") (pinfunction "1_1") (pintype "passive"))
      (node (ref "U4") (pin "M1") (pinfunction "SCLK_AUX_M1") (pintype "input"))
    )
    (net (code "99") (name "Net-(U4A-SDIO_AUX)") (class "Default")
      (node (ref "R70") (pin "2") (pinfunction "2_2") (pintype "passive"))
      (node (ref "U4") (pin "L1") (pinfunction "SDIO_AUX_L1") (pintype "bidirectional"))
    )
    (net (code "100") (name "Net-(U4A-SDI_A1_AUX)") (class "Default")
      (node (ref "R63") (pin "1") (pinfunction "1_1") (pintype "passive"))
      (node (ref "U4") (pin "K1") (pinfunction "SDI_A1_AUX_K1") (pintype "input"))
    )
    (net (code "101") (name "Net-(U4A-nTEST)") (class "Default")
      (node (ref "R16") (pin "1") (pinfunction "1_1") (pintype "passive"))
      (node (ref "U4") (pin "M10") (pinfunction "nTEST_M10") (pintype "input"))
    )
    (net (code "102") (name "Net-(U5-A1)") (class "Default")
      (node (ref "R68") (pin "1") (pinfunction "1_1") (pintype "passive"))
      (node (ref "R69") (pin "2") (pinfunction "2_2") (pintype "passive"))
      (node (ref "U5") (pin "2") (pinfunction "A1_2") (pintype "input"))
    )
    (net (code "103") (name "Net-(U5-A2)") (class "Default")
      (node (ref "R67") (pin "1") (pinfunction "1_1") (pintype "passive"))
      (node (ref "R74") (pin "1") (pinfunction "1_1") (pintype "passive"))
      (node (ref "U5") (pin "3") (pinfunction "A2_3") (pintype "input"))
    )
    (net (code "104") (name "Net-(U5-WP)") (class "Default")
      (node (ref "R71") (pin "2") (pinfunction "2_2") (pintype "passive"))
      (node (ref "U5") (pin "7") (pinfunction "WP_7") (pintype "input"))
    )
    (net (code "105") (name "P3V3") (class "Default")
      (node (ref "C28") (pin "1") (pinfunction "1_1") (pintype "passive"))
      (node (ref "D4") (pin "2") (pinfunction "A_2") (pintype "passive"))
      (node (ref "R16") (pin "2") (pinfunction "2_2") (pintype "passive"))
      (node (ref "R17") (pin "1") (pinfunction "1_1") (pintype "passive"))
      (node (ref "R25") (pin "1") (pinfunction "1_1") (pintype "passive"))
      (node (ref "R26") (pin "1") (pinfunction "1_1") (pintype "passive"))
      (node (ref "R30") (pin "1") (pinfunction "1_1") (pintype "passive"))
      (node (ref "R43") (pin "1") (pinfunction "1_1") (pintype "passive"))
      (node (ref "R45") (pin "1") (pinfunction "1_1") (pintype "passive"))
      (node (ref "R57") (pin "1") (pinfunction "1_1") (pintype "passive"))
      (node (ref "R64") (pin "1") (pinfunction "1_1") (pintype "passive"))
      (node (ref "R65") (pin "1") (pinfunction "1_1") (pintype "passive"))
      (node (ref "R66") (pin "1") (pinfunction "1_1") (pintype "passive"))
      (node (ref "R67") (pin "2") (pinfunction "2_2") (pintype "passive"))
      (node (ref "R68") (pin "2") (pinfunction "2_2") (pintype "passive"))
      (node (ref "U5") (pin "8") (pinfunction "VCC_8") (pintype "power_in"))
    )
    (net (code "106") (name "PD9") (class "Default")
      (node (ref "R43") (pin "2") (pinfunction "2_2") (pintype "passive"))
      (node (ref "U4") (pin "A10") (pinfunction "GPIO[0]_A10") (pintype "bidirectional"))
    )
    (net (code "107") (name "PD10") (class "Default")
      (node (ref "R45") (pin "2") (pinfunction "2_2") (pintype "passive"))
      (node (ref "U4") (pin "J11") (pinfunction "GPIO[3]_J11") (pintype "bidirectional"))
    )
    (net (code "108") (name "PD14") (class "Default")
      (node (ref "R57") (pin "2") (pinfunction "2_2") (pintype "passive"))
      (node (ref "U4") (pin "A5") (pinfunction "GPIO[13]_A5") (pintype "bidirectional"))
    )
    (net (code "109") (name "PHY_REFCLK_50M") (class "Default")
      (node (ref "U4") (pin "M9") (pinfunction "Q6_M9") (pintype "output"))
    )
    (net (code "110") (name "SX1276_DIO0") (class "Default")
      (node (ref "U4") (pin "B2") (pinfunction "nCLK0_B2") (pintype "input"))
    )
    (net (code "111") (name "TIM2_CH1") (class "Default")
      (node (ref "U4") (pin "B1") (pinfunction "CLK0_B1") (pintype "input"))
    )
    (net (code "112") (name "TIM2_CH2") (class "Default")
      (node (ref "U4") (pin "C1") (pinfunction "CLK1_C1") (pintype "input"))
    )
    (net (code "113") (name "TIM2_ETR") (class "Default")
      (node (ref "U4") (pin "A6") (pinfunction "Q8_A6") (pintype "output"))
    )
    (net (code "114") (name "unconnected-(U4B-TP1-PadM7)") (class "Default")
      (node (ref "U4") (pin "M7") (pinfunction "TP1_M7") (pintype "passive"))
    )
    (net (code "115") (name "unconnected-(U4B-TP2-PadL7)") (class "Default")
      (node (ref "U4") (pin "L7") (pinfunction "TP2_L7") (pintype "passive"))
    )
    (net (code "116") (name "unconnected-(U5-NC-Pad1)") (class "Default")
      (node (ref "U5") (pin "1") (pinfunction "NC_1") (pintype "passive"))
    )
  )
)
